# LME49600_HPA.net
KiCad netlist of a schematic drawn in EAGLE
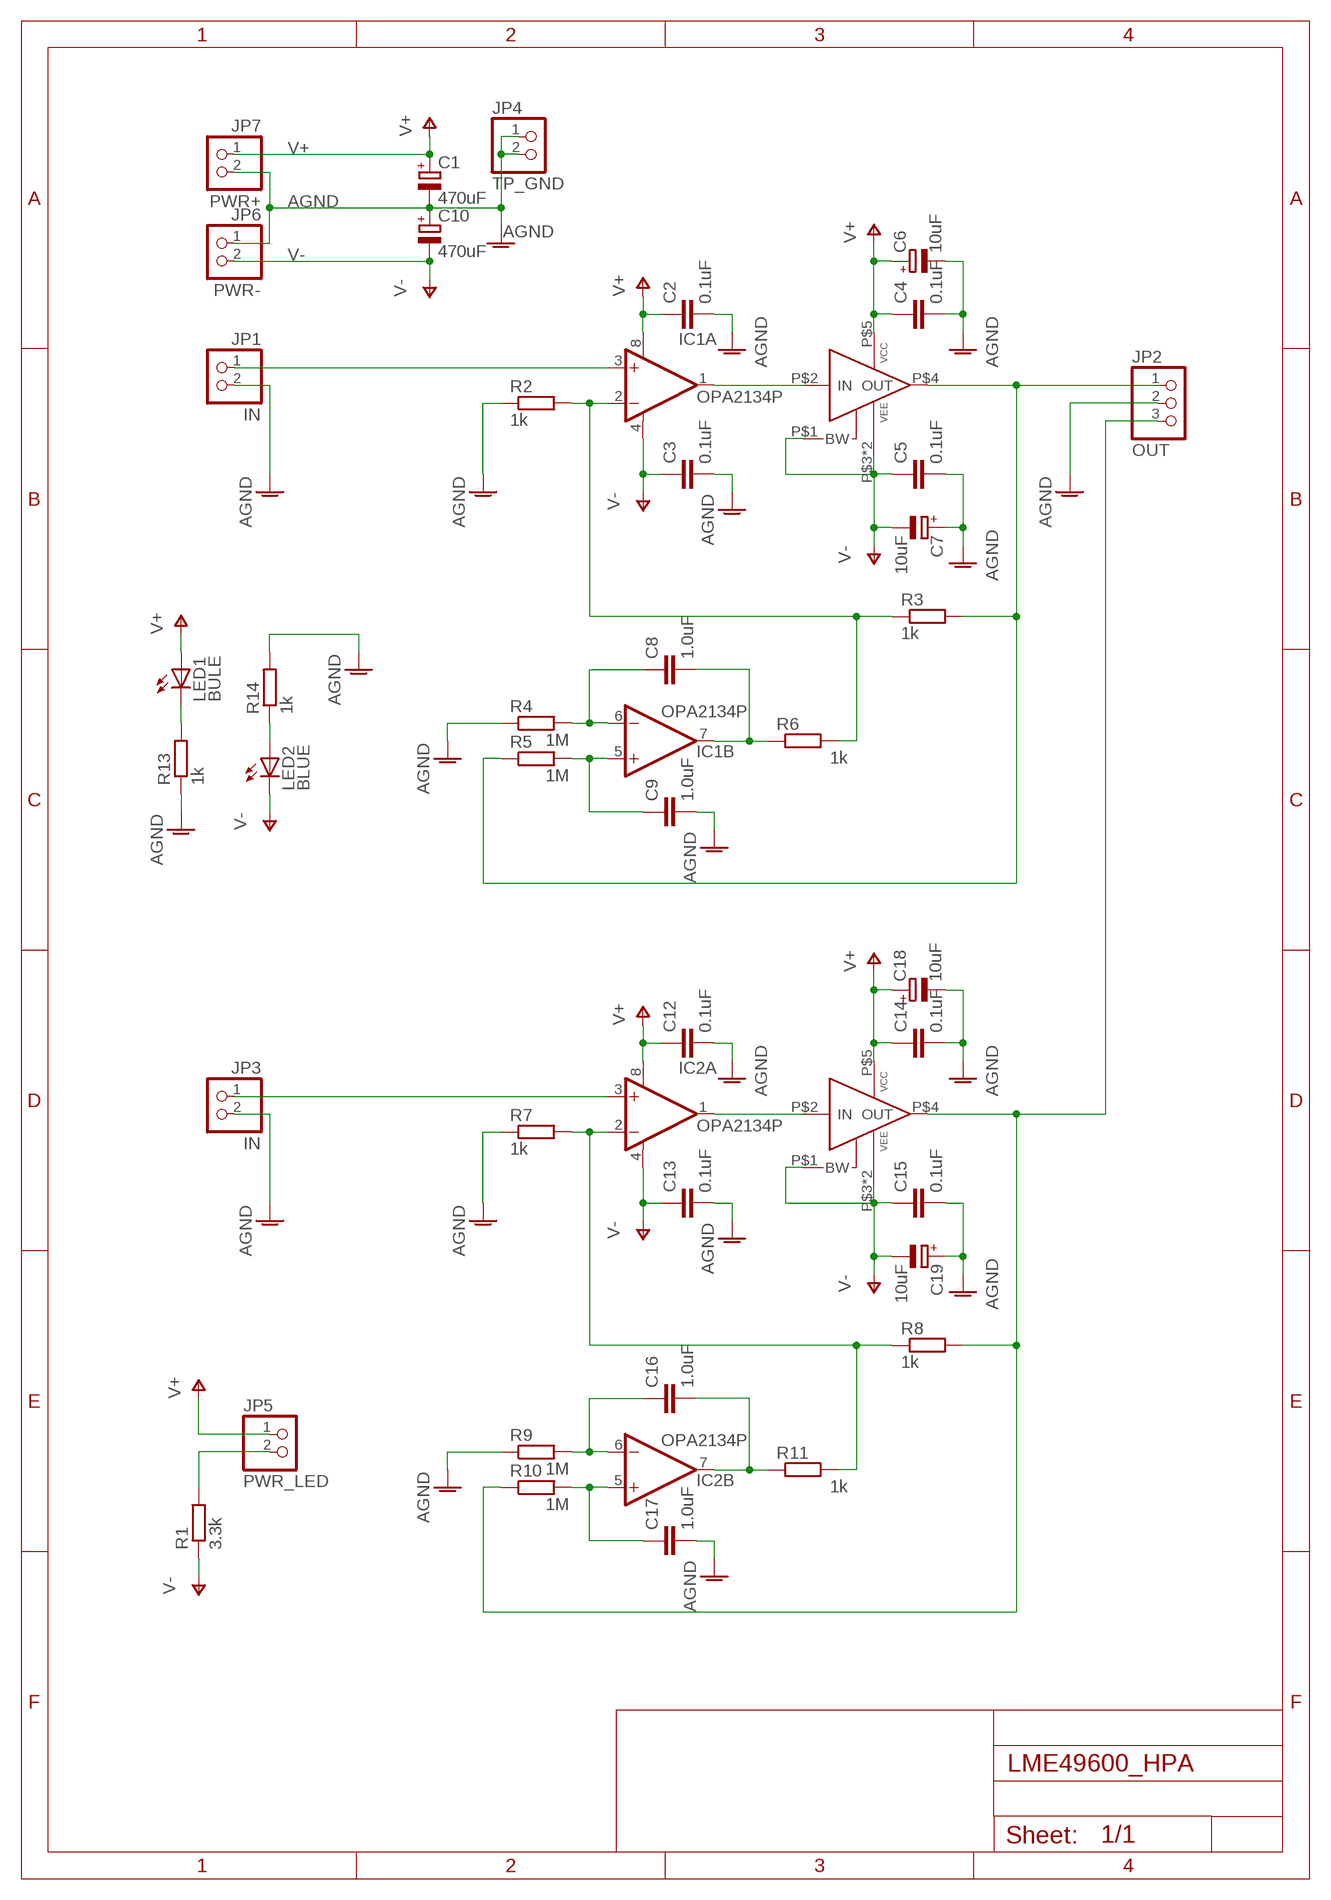
[diagram p0: schematic, sheet 1]

(export (version "E")
  (design (tool "Eeschema 10.0.6"))
  (components
    (comp (ref "C1")
      (value "470uF")
      (footprint "eagle-import:E7,5-16")
      (libsource (lib "eagle-import") (part "CPOL-EUE7.5-16"))
    )
    (comp (ref "C2")
      (value "0.1uF")
      (footprint "eagle-import:C025-024X044")
      (libsource (lib "eagle-import") (part "C-EU025-024X044"))
    )
    (comp (ref "C3")
      (value "0.1uF")
      (footprint "eagle-import:C025-024X044")
      (libsource (lib "eagle-import") (part "C-EU025-024X044"))
    )
    (comp (ref "C4")
      (value "0.1uF")
      (footprint "eagle-import:C025-024X044")
      (libsource (lib "eagle-import") (part "C-EU025-024X044"))
    )
    (comp (ref "C5")
      (value "0.1uF")
      (footprint "eagle-import:C025-024X044")
      (libsource (lib "eagle-import") (part "C-EU025-024X044"))
    )
    (comp (ref "C6")
      (value "10uF")
      (footprint "eagle-import:E2,5-5")
      (libsource (lib "eagle-import") (part "CPOL-EUE2.5-5"))
    )
    (comp (ref "C7")
      (value "10uF")
      (footprint "eagle-import:E2,5-5")
      (libsource (lib "eagle-import") (part "CPOL-EUE2.5-5"))
    )
    (comp (ref "C8")
      (value "1.0uF")
      (footprint "eagle-import:C050-050X075")
      (libsource (lib "eagle-import") (part "C-EU050-050X075"))
    )
    (comp (ref "C9")
      (value "1.0uF")
      (footprint "eagle-import:C050-050X075")
      (libsource (lib "eagle-import") (part "C-EU050-050X075"))
    )
    (comp (ref "C10")
      (value "470uF")
      (footprint "eagle-import:E7,5-16")
      (libsource (lib "eagle-import") (part "CPOL-EUE7.5-16"))
    )
    (comp (ref "C12")
      (value "0.1uF")
      (footprint "eagle-import:C025-024X044")
      (libsource (lib "eagle-import") (part "C-EU025-024X044"))
    )
    (comp (ref "C13")
      (value "0.1uF")
      (footprint "eagle-import:C025-024X044")
      (libsource (lib "eagle-import") (part "C-EU025-024X044"))
    )
    (comp (ref "C14")
      (value "0.1uF")
      (footprint "eagle-import:C025-024X044")
      (libsource (lib "eagle-import") (part "C-EU025-024X044"))
    )
    (comp (ref "C15")
      (value "0.1uF")
      (footprint "eagle-import:C025-024X044")
      (libsource (lib "eagle-import") (part "C-EU025-024X044"))
    )
    (comp (ref "C16")
      (value "1.0uF")
      (footprint "eagle-import:C050-050X075")
      (libsource (lib "eagle-import") (part "C-EU050-050X075"))
    )
    (comp (ref "C17")
      (value "1.0uF")
      (footprint "eagle-import:C050-050X075")
      (libsource (lib "eagle-import") (part "C-EU050-050X075"))
    )
    (comp (ref "C18")
      (value "10uF")
      (footprint "eagle-import:E2,5-5")
      (libsource (lib "eagle-import") (part "CPOL-EUE2.5-5"))
    )
    (comp (ref "C19")
      (value "10uF")
      (footprint "eagle-import:E2,5-5")
      (libsource (lib "eagle-import") (part "CPOL-EUE2.5-5"))
    )
    (comp (ref "IC1")
      (value "OPA2134P")
      (footprint "eagle-import:DIL08")
      (fields (field (name "MF") "TEXAS INSTRUMENTS") (field (name "MPN") "OPA2134PA"))
      (libsource (lib "eagle-import") (part "OPA2134P"))
    )
    (comp (ref "IC2")
      (value "OPA2134P")
      (footprint "eagle-import:DIL08")
      (fields (field (name "MF") "TEXAS INSTRUMENTS") (field (name "MPN") "OPA2134PA"))
      (libsource (lib "eagle-import") (part "OPA2134P"))
    )
    (comp (ref "JP1")
      (value "IN")
      (footprint "eagle-import:1X02")
      (libsource (lib "eagle-import") (part "PINHD-1X2"))
    )
    (comp (ref "JP2")
      (value "OUT")
      (footprint "eagle-import:1X03")
      (libsource (lib "eagle-import") (part "PINHD-1X3"))
    )
    (comp (ref "JP3")
      (value "IN")
      (footprint "eagle-import:1X02")
      (libsource (lib "eagle-import") (part "PINHD-1X2"))
    )
    (comp (ref "JP4")
      (value "TP_GND")
      (footprint "eagle-import:1X02")
      (libsource (lib "eagle-import") (part "PINHD-1X2"))
    )
    (comp (ref "JP5")
      (value "PWR_LED")
      (footprint "eagle-import:1X02")
      (libsource (lib "eagle-import") (part "PINHD-1X2"))
    )
    (comp (ref "JP6")
      (value "PWR-")
      (footprint "eagle-import:1X02")
      (libsource (lib "eagle-import") (part "PINHD-1X2"))
    )
    (comp (ref "JP7")
      (value "PWR+")
      (footprint "eagle-import:1X02")
      (libsource (lib "eagle-import") (part "PINHD-1X2"))
    )
    (comp (ref "LED1")
      (value "BULE")
      (footprint "eagle-import:LED3MM")
      (libsource (lib "eagle-import") (part "LED3MM"))
    )
    (comp (ref "LED2")
      (value "BLUE")
      (footprint "eagle-import:LED3MM")
      (libsource (lib "eagle-import") (part "LED3MM"))
    )
    (comp (ref "R1")
      (value "3.3k")
      (footprint "eagle-import:0207_7")
      (libsource (lib "eagle-import") (part "R-EU_0207/7"))
    )
    (comp (ref "R2")
      (value "1k")
      (footprint "eagle-import:0207_7")
      (libsource (lib "eagle-import") (part "R-EU_0207/7"))
    )
    (comp (ref "R3")
      (value "1k")
      (footprint "eagle-import:0207_7")
      (libsource (lib "eagle-import") (part "R-EU_0207/7"))
    )
    (comp (ref "R4")
      (value "1M")
      (footprint "eagle-import:0207_7")
      (libsource (lib "eagle-import") (part "R-EU_0207/7"))
    )
    (comp (ref "R5")
      (value "1M")
      (footprint "eagle-import:0207_7")
      (libsource (lib "eagle-import") (part "R-EU_0207/7"))
    )
    (comp (ref "R6")
      (value "1k")
      (footprint "eagle-import:0207_7")
      (libsource (lib "eagle-import") (part "R-EU_0207/7"))
    )
    (comp (ref "R7")
      (value "1k")
      (footprint "eagle-import:0207_7")
      (libsource (lib "eagle-import") (part "R-EU_0207/7"))
    )
    (comp (ref "R8")
      (value "1k")
      (footprint "eagle-import:0207_7")
      (libsource (lib "eagle-import") (part "R-EU_0207/7"))
    )
    (comp (ref "R9")
      (value "1M")
      (footprint "eagle-import:0207_7")
      (libsource (lib "eagle-import") (part "R-EU_0207/7"))
    )
    (comp (ref "R10")
      (value "1M")
      (footprint "eagle-import:0207_7")
      (libsource (lib "eagle-import") (part "R-EU_0207/7"))
    )
    (comp (ref "R11")
      (value "1k")
      (footprint "eagle-import:0207_7")
      (libsource (lib "eagle-import") (part "R-EU_0207/7"))
    )
    (comp (ref "R13")
      (value "1k")
      (footprint "eagle-import:0207_7")
      (libsource (lib "eagle-import") (part "R-EU_0207/7"))
    )
    (comp (ref "R14")
      (value "1k")
      (footprint "eagle-import:0207_7")
      (libsource (lib "eagle-import") (part "R-EU_0207/7"))
    )
    (comp (ref "U$1")
      (value "LME49600-BRD3")
      (footprint "eagle-import:TO-263-5L")
      (libsource (lib "eagle-import") (part "LME49600-BRD3"))
    )
    (comp (ref "U$2")
      (value "LME49600-BRD3")
      (footprint "eagle-import:TO-263-5L")
      (libsource (lib "eagle-import") (part "LME49600-BRD3"))
    )
  )
  (nets
    (net (code "1") (name "AGND") (class "Default")
      (node (ref "C1") (pin "-") (pinfunction "-_-") (pintype "passive"))
      (node (ref "C10") (pin "+") (pinfunction "+_+") (pintype "passive"))
      (node (ref "C12") (pin "2") (pinfunction "2_2") (pintype "passive"))
      (node (ref "C13") (pin "2") (pinfunction "2_2") (pintype "passive"))
      (node (ref "C14") (pin "2") (pinfunction "2_2") (pintype "passive"))
      (node (ref "C15") (pin "2") (pinfunction "2_2") (pintype "passive"))
      (node (ref "C17") (pin "2") (pinfunction "2_2") (pintype "passive"))
      (node (ref "C18") (pin "-") (pinfunction "-_-") (pintype "passive"))
      (node (ref "C19") (pin "+") (pinfunction "+_+") (pintype "passive"))
      (node (ref "C2") (pin "2") (pinfunction "2_2") (pintype "passive"))
      (node (ref "C3") (pin "2") (pinfunction "2_2") (pintype "passive"))
      (node (ref "C4") (pin "2") (pinfunction "2_2") (pintype "passive"))
      (node (ref "C5") (pin "2") (pinfunction "2_2") (pintype "passive"))
      (node (ref "C6") (pin "-") (pinfunction "-_-") (pintype "passive"))
      (node (ref "C7") (pin "+") (pinfunction "+_+") (pintype "passive"))
      (node (ref "C9") (pin "2") (pinfunction "2_2") (pintype "passive"))
      (node (ref "JP1") (pin "2") (pinfunction "2_2") (pintype "passive"))
      (node (ref "JP2") (pin "2") (pinfunction "2_2") (pintype "passive"))
      (node (ref "JP3") (pin "2") (pinfunction "2_2") (pintype "passive"))
      (node (ref "JP4") (pin "1") (pinfunction "1_1") (pintype "passive"))
      (node (ref "JP4") (pin "2") (pinfunction "2_2") (pintype "passive"))
      (node (ref "JP6") (pin "1") (pinfunction "1_1") (pintype "passive"))
      (node (ref "JP7") (pin "2") (pinfunction "2_2") (pintype "passive"))
      (node (ref "R13") (pin "1") (pinfunction "1_1") (pintype "passive"))
      (node (ref "R14") (pin "2") (pinfunction "2_2") (pintype "passive"))
      (node (ref "R2") (pin "1") (pinfunction "1_1") (pintype "passive"))
      (node (ref "R4") (pin "1") (pinfunction "1_1") (pintype "passive"))
      (node (ref "R7") (pin "1") (pinfunction "1_1") (pintype "passive"))
      (node (ref "R9") (pin "1") (pinfunction "1_1") (pintype "passive"))
    )
    (net (code "2") (name "Net-(IC1A-+IN)") (class "Default")
      (node (ref "IC1") (pin "3") (pinfunction "+IN_3") (pintype "input"))
      (node (ref "JP1") (pin "1") (pinfunction "1_1") (pintype "passive"))
    )
    (net (code "3") (name "Net-(IC1A--IN)") (class "Default")
      (node (ref "IC1") (pin "2") (pinfunction "-IN_2") (pintype "input"))
      (node (ref "R2") (pin "2") (pinfunction "2_2") (pintype "passive"))
      (node (ref "R3") (pin "1") (pinfunction "1_1") (pintype "passive"))
      (node (ref "R6") (pin "2") (pinfunction "2_2") (pintype "passive"))
    )
    (net (code "4") (name "Net-(IC1A-OUT)") (class "Default")
      (node (ref "IC1") (pin "1") (pinfunction "OUT_1") (pintype "output"))
      (node (ref "U$1") (pin "P$2") (pinfunction "IN_P$2") (pintype "input"))
    )
    (net (code "5") (name "Net-(IC1B-+IN)") (class "Default")
      (node (ref "C9") (pin "1") (pinfunction "1_1") (pintype "passive"))
      (node (ref "IC1") (pin "5") (pinfunction "+IN_5") (pintype "input"))
      (node (ref "R5") (pin "2") (pinfunction "2_2") (pintype "passive"))
    )
    (net (code "6") (name "Net-(IC1B--IN)") (class "Default")
      (node (ref "C8") (pin "1") (pinfunction "1_1") (pintype "passive"))
      (node (ref "IC1") (pin "6") (pinfunction "-IN_6") (pintype "input"))
      (node (ref "R4") (pin "2") (pinfunction "2_2") (pintype "passive"))
    )
    (net (code "7") (name "Net-(IC1B-OUT)") (class "Default")
      (node (ref "C8") (pin "2") (pinfunction "2_2") (pintype "passive"))
      (node (ref "IC1") (pin "7") (pinfunction "OUT_7") (pintype "output"))
      (node (ref "R6") (pin "1") (pinfunction "1_1") (pintype "passive"))
    )
    (net (code "8") (name "Net-(IC2A-+IN)") (class "Default")
      (node (ref "IC2") (pin "3") (pinfunction "+IN_3") (pintype "input"))
      (node (ref "JP3") (pin "1") (pinfunction "1_1") (pintype "passive"))
    )
    (net (code "9") (name "Net-(IC2A--IN)") (class "Default")
      (node (ref "IC2") (pin "2") (pinfunction "-IN_2") (pintype "input"))
      (node (ref "R11") (pin "2") (pinfunction "2_2") (pintype "passive"))
      (node (ref "R7") (pin "2") (pinfunction "2_2") (pintype "passive"))
      (node (ref "R8") (pin "1") (pinfunction "1_1") (pintype "passive"))
    )
    (net (code "10") (name "Net-(IC2A-OUT)") (class "Default")
      (node (ref "IC2") (pin "1") (pinfunction "OUT_1") (pintype "output"))
      (node (ref "U$2") (pin "P$2") (pinfunction "IN_P$2") (pintype "input"))
    )
    (net (code "11") (name "Net-(IC2B-+IN)") (class "Default")
      (node (ref "C17") (pin "1") (pinfunction "1_1") (pintype "passive"))
      (node (ref "IC2") (pin "5") (pinfunction "+IN_5") (pintype "input"))
      (node (ref "R10") (pin "2") (pinfunction "2_2") (pintype "passive"))
    )
    (net (code "12") (name "Net-(IC2B--IN)") (class "Default")
      (node (ref "C16") (pin "1") (pinfunction "1_1") (pintype "passive"))
      (node (ref "IC2") (pin "6") (pinfunction "-IN_6") (pintype "input"))
      (node (ref "R9") (pin "2") (pinfunction "2_2") (pintype "passive"))
    )
    (net (code "13") (name "Net-(IC2B-OUT)") (class "Default")
      (node (ref "C16") (pin "2") (pinfunction "2_2") (pintype "passive"))
      (node (ref "IC2") (pin "7") (pinfunction "OUT_7") (pintype "output"))
      (node (ref "R11") (pin "1") (pinfunction "1_1") (pintype "passive"))
    )
    (net (code "14") (name "Net-(JP5-Pad2)") (class "Default")
      (node (ref "JP5") (pin "2") (pinfunction "2_2") (pintype "passive"))
      (node (ref "R1") (pin "2") (pinfunction "2_2") (pintype "passive"))
    )
    (net (code "15") (name "Net-(LED1-C)") (class "Default")
      (node (ref "LED1") (pin "K") (pinfunction "C_K") (pintype "passive"))
      (node (ref "R13") (pin "2") (pinfunction "2_2") (pintype "passive"))
    )
    (net (code "16") (name "Net-(LED2-PadA)") (class "Default")
      (node (ref "LED2") (pin "A") (pinfunction "A_A") (pintype "passive"))
      (node (ref "R14") (pin "1") (pinfunction "1_1") (pintype "passive"))
    )
    (net (code "17") (name "Net-(U$1-OUT)") (class "Default")
      (node (ref "JP2") (pin "1") (pinfunction "1_1") (pintype "passive"))
      (node (ref "R3") (pin "2") (pinfunction "2_2") (pintype "passive"))
      (node (ref "R5") (pin "1") (pinfunction "1_1") (pintype "passive"))
      (node (ref "U$1") (pin "P$4") (pinfunction "OUT_P$4") (pintype "output"))
    )
    (net (code "18") (name "Net-(U$2-OUT)") (class "Default")
      (node (ref "JP2") (pin "3") (pinfunction "3_3") (pintype "passive"))
      (node (ref "R10") (pin "1") (pinfunction "1_1") (pintype "passive"))
      (node (ref "R8") (pin "2") (pinfunction "2_2") (pintype "passive"))
      (node (ref "U$2") (pin "P$4") (pinfunction "OUT_P$4") (pintype "output"))
    )
    (net (code "19") (name "V+") (class "Default")
      (node (ref "C1") (pin "+") (pinfunction "+_+") (pintype "passive"))
      (node (ref "C12") (pin "1") (pinfunction "1_1") (pintype "passive"))
      (node (ref "C14") (pin "1") (pinfunction "1_1") (pintype "passive"))
      (node (ref "C18") (pin "+") (pinfunction "+_+") (pintype "passive"))
      (node (ref "C2") (pin "1") (pinfunction "1_1") (pintype "passive"))
      (node (ref "C4") (pin "1") (pinfunction "1_1") (pintype "passive"))
      (node (ref "C6") (pin "+") (pinfunction "+_+") (pintype "passive"))
      (node (ref "IC1") (pin "8") (pinfunction "V+_8") (pintype "power_in"))
      (node (ref "IC2") (pin "8") (pinfunction "V+_8") (pintype "power_in"))
      (node (ref "JP5") (pin "1") (pinfunction "1_1") (pintype "passive"))
      (node (ref "JP7") (pin "1") (pinfunction "1_1") (pintype "passive"))
      (node (ref "LED1") (pin "A") (pinfunction "A_A") (pintype "passive"))
      (node (ref "U$1") (pin "P$5") (pinfunction "VCC_P$5") (pintype "power_in"))
      (node (ref "U$2") (pin "P$5") (pinfunction "VCC_P$5") (pintype "power_in"))
    )
    (net (code "20") (name "V-") (class "Default")
      (node (ref "C10") (pin "-") (pinfunction "-_-") (pintype "passive"))
      (node (ref "C13") (pin "1") (pinfunction "1_1") (pintype "passive"))
      (node (ref "C15") (pin "1") (pinfunction "1_1") (pintype "passive"))
      (node (ref "C19") (pin "-") (pinfunction "-_-") (pintype "passive"))
      (node (ref "C3") (pin "1") (pinfunction "1_1") (pintype "passive"))
      (node (ref "C5") (pin "1") (pinfunction "1_1") (pintype "passive"))
      (node (ref "C7") (pin "-") (pinfunction "-_-") (pintype "passive"))
      (node (ref "IC1") (pin "4") (pinfunction "V-_4") (pintype "power_in"))
      (node (ref "IC2") (pin "4") (pinfunction "V-_4") (pintype "power_in"))
      (node (ref "JP6") (pin "2") (pinfunction "2_2") (pintype "passive"))
      (node (ref "LED2") (pin "K") (pinfunction "C_K") (pintype "passive"))
      (node (ref "R1") (pin "1") (pinfunction "1_1") (pintype "passive"))
      (node (ref "U$1") (pin "P$1") (pinfunction "BW_P$1") (pintype "input"))
      (node (ref "U$1") (pin "P$3") (pinfunction "VEE_P$3") (pintype "power_in"))
      (node (ref "U$1") (pin "P$6") (pinfunction "VEE_P$6") (pintype "power_in"))
      (node (ref "U$2") (pin "P$1") (pinfunction "BW_P$1") (pintype "input"))
      (node (ref "U$2") (pin "P$3") (pinfunction "VEE_P$3") (pintype "power_in"))
      (node (ref "U$2") (pin "P$6") (pinfunction "VEE_P$6") (pintype "power_in"))
    )
  )
)
